# platform_smd2_map2.net
KiCad netlist of a schematic drawn in EAGLE
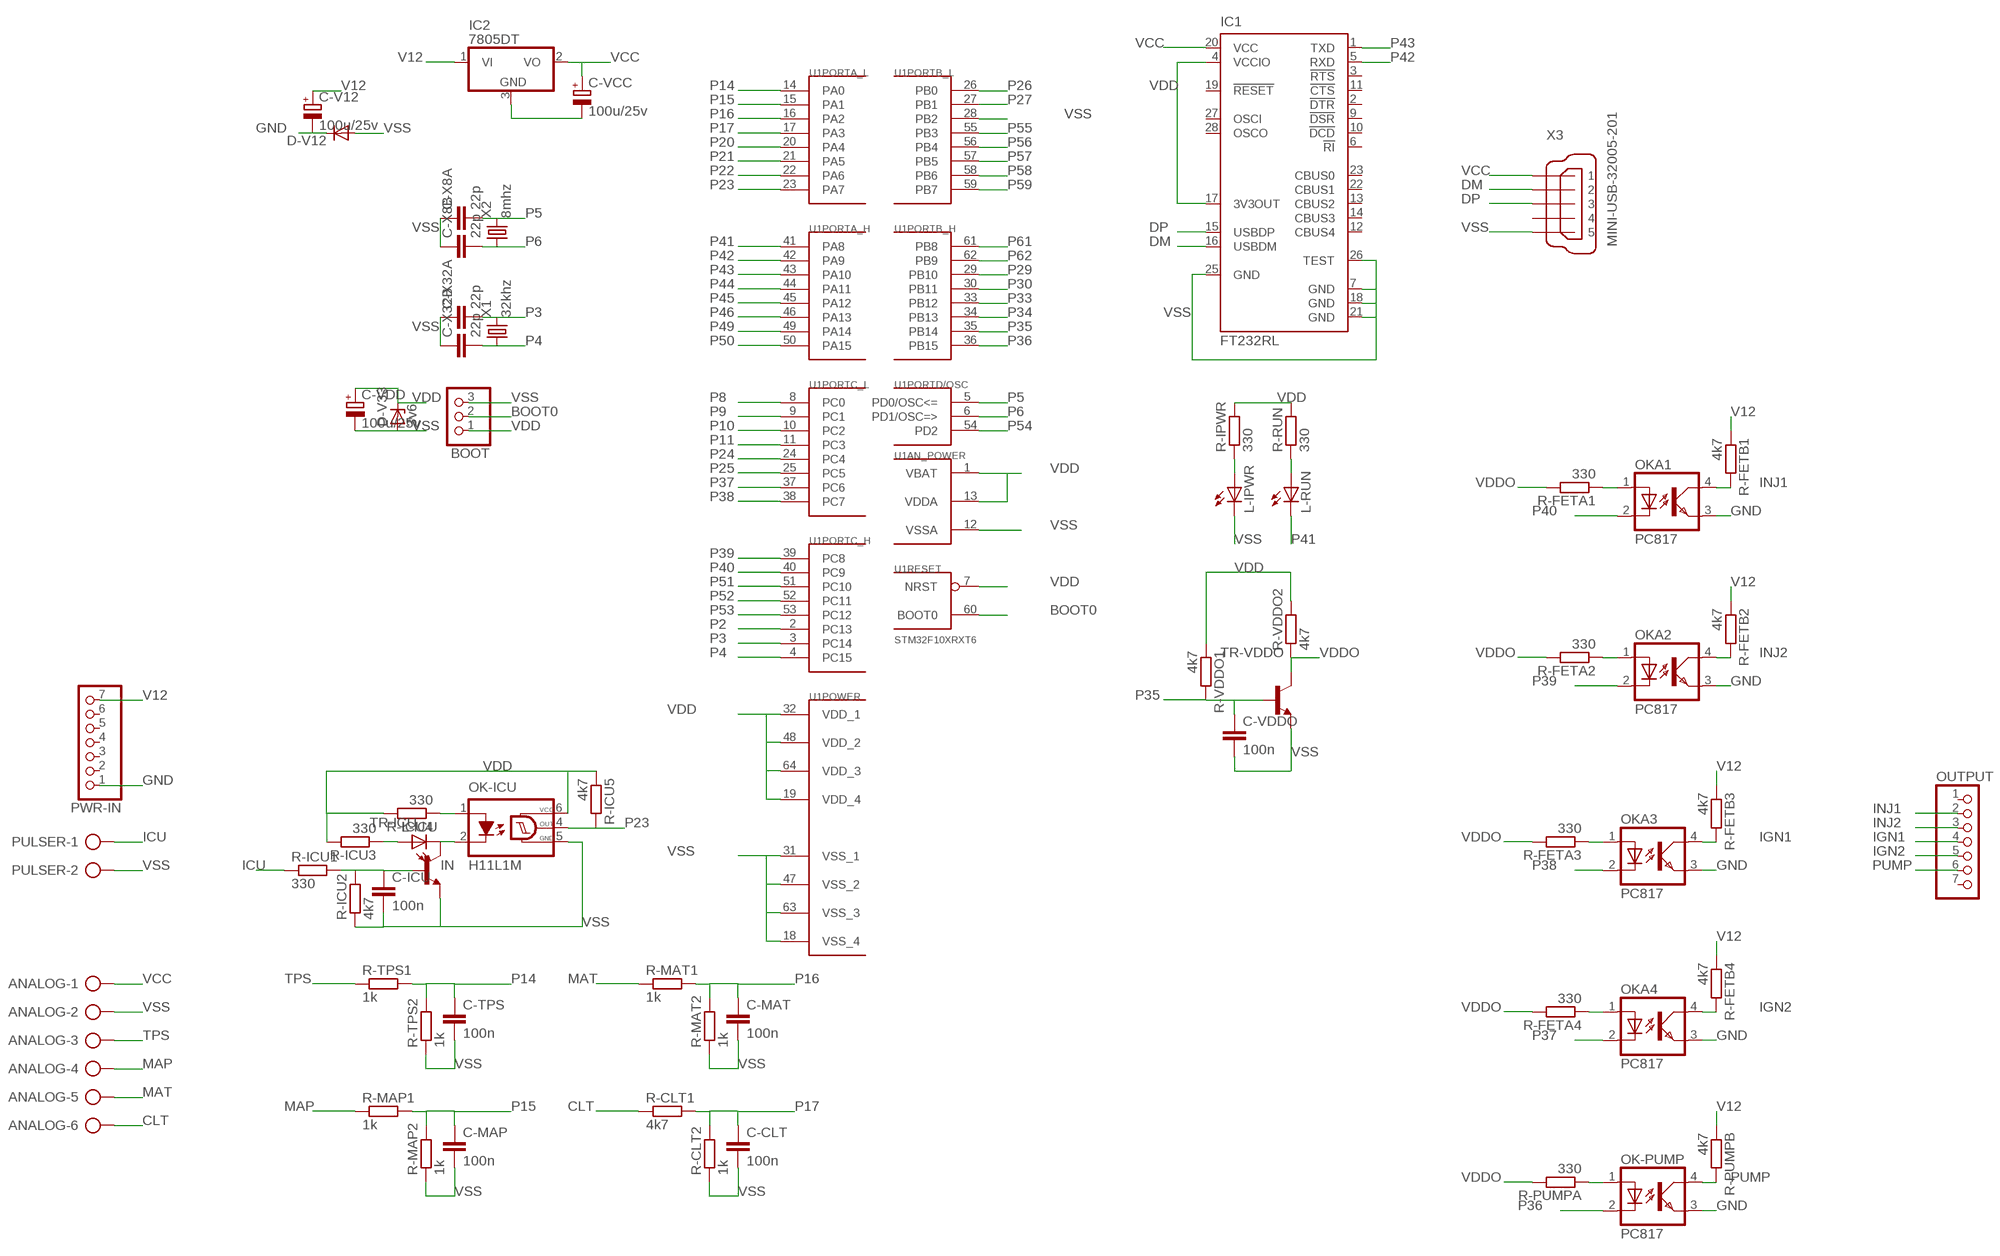
[diagram p0: schematic, sheet 1]

(export (version "E")
  (design (tool "Eeschema 10.0.6"))
  (components
    (comp (ref "ANALOG")
      (value "AK300/6")
      (footprint "eagle-import:AK300_6")
      (libsource (lib "eagle-import") (part "AK300/6"))
    )
    (comp (ref "BOOT")
      (value "PINHD-1X3")
      (footprint "eagle-import:1X03")
      (libsource (lib "eagle-import") (part "PINHD-1X3"))
    )
    (comp (ref "C-CLT")
      (value "100n")
      (footprint "eagle-import:C1206")
      (libsource (lib "eagle-import") (part "C-EUC1206"))
    )
    (comp (ref "C-ICU")
      (value "100n")
      (footprint "eagle-import:C1206")
      (libsource (lib "eagle-import") (part "C-EUC1206"))
    )
    (comp (ref "C-MAP")
      (value "100n")
      (footprint "eagle-import:C1206")
      (libsource (lib "eagle-import") (part "C-EUC1206"))
    )
    (comp (ref "C-MAT")
      (value "100n")
      (footprint "eagle-import:C1206")
      (libsource (lib "eagle-import") (part "C-EUC1206"))
    )
    (comp (ref "C-TPS")
      (value "100n")
      (footprint "eagle-import:C1206")
      (libsource (lib "eagle-import") (part "C-EUC1206"))
    )
    (comp (ref "C-V12")
      (value "100u/25v")
      (footprint "eagle-import:PANASONIC_D")
      (libsource (lib "eagle-import") (part "CPOL-EUD"))
    )
    (comp (ref "C-VCC")
      (value "100u/25v")
      (footprint "eagle-import:PANASONIC_D")
      (libsource (lib "eagle-import") (part "CPOL-EUD"))
    )
    (comp (ref "C-VDD")
      (value "100u/25v")
      (footprint "eagle-import:PANASONIC_D")
      (libsource (lib "eagle-import") (part "CPOL-EUD"))
    )
    (comp (ref "C-VDDO")
      (value "100n")
      (footprint "eagle-import:C1206")
      (libsource (lib "eagle-import") (part "C-EUC1206"))
    )
    (comp (ref "C-X8A")
      (value "22p")
      (footprint "eagle-import:C1206")
      (libsource (lib "eagle-import") (part "C-EUC1206"))
    )
    (comp (ref "C-X8B")
      (value "22p")
      (footprint "eagle-import:C1206")
      (libsource (lib "eagle-import") (part "C-EUC1206"))
    )
    (comp (ref "C-X32A")
      (value "22p")
      (footprint "eagle-import:C1206")
      (libsource (lib "eagle-import") (part "C-EUC1206"))
    )
    (comp (ref "C-X32B")
      (value "22p")
      (footprint "eagle-import:C1206")
      (libsource (lib "eagle-import") (part "C-EUC1206"))
    )
    (comp (ref "D-V12")
      (value "DIODE-SMB")
      (footprint "eagle-import:SMB")
      (libsource (lib "eagle-import") (part "DIODE-SMB"))
    )
    (comp (ref "D-V33")
      (value "3v6")
      (footprint "eagle-import:SMB")
      (libsource (lib "eagle-import") (part "ZENER-DIODESMB"))
    )
    (comp (ref "IC1")
      (value "FT232RL")
      (footprint "eagle-import:SSOP28")
      (libsource (lib "eagle-import") (part "FT232RL"))
    )
    (comp (ref "IC2")
      (value "7805DT")
      (footprint "eagle-import:TO252")
      (libsource (lib "eagle-import") (part "78DT05"))
    )
    (comp (ref "L-ICU")
      (value "LEDSMT1206")
      (footprint "eagle-import:1206")
      (libsource (lib "eagle-import") (part "LEDSMT1206"))
    )
    (comp (ref "L-IPWR")
      (value "LEDSMT1206")
      (footprint "eagle-import:1206")
      (libsource (lib "eagle-import") (part "LEDSMT1206"))
    )
    (comp (ref "L-RUN")
      (value "LEDSMT1206")
      (footprint "eagle-import:1206")
      (libsource (lib "eagle-import") (part "LEDSMT1206"))
    )
    (comp (ref "OK-ICU")
      (value "H11L1M")
      (footprint "eagle-import:DIL06")
      (fields (field (name "MF") "FAIRCHILD SEMICONDUCTOR") (field (name "MPN") "H11L1-M"))
      (libsource (lib "eagle-import") (part "H11LM1"))
    )
    (comp (ref "OK-PUMP")
      (value "PC817")
      (footprint "eagle-import:DIL04")
      (fields (field (name "MPN") "PC817X4J000F"))
      (libsource (lib "eagle-import") (part "PC817"))
    )
    (comp (ref "OKA1")
      (value "PC817")
      (footprint "eagle-import:DIL04")
      (fields (field (name "MPN") "PC817X4J000F"))
      (libsource (lib "eagle-import") (part "PC817"))
    )
    (comp (ref "OKA2")
      (value "PC817")
      (footprint "eagle-import:DIL04")
      (fields (field (name "MPN") "PC817X4J000F"))
      (libsource (lib "eagle-import") (part "PC817"))
    )
    (comp (ref "OKA3")
      (value "PC817")
      (footprint "eagle-import:DIL04")
      (fields (field (name "MPN") "PC817X4J000F"))
      (libsource (lib "eagle-import") (part "PC817"))
    )
    (comp (ref "OKA4")
      (value "PC817")
      (footprint "eagle-import:DIL04")
      (fields (field (name "MPN") "PC817X4J000F"))
      (libsource (lib "eagle-import") (part "PC817"))
    )
    (comp (ref "OUTPUT")
      (value "PINHD-1X7")
      (footprint "eagle-import:1X07")
      (libsource (lib "eagle-import") (part "PINHD-1X7"))
    )
    (comp (ref "PULSER")
      (value "AK300/2")
      (footprint "eagle-import:AK300_2")
      (libsource (lib "eagle-import") (part "AK300/2"))
    )
    (comp (ref "PWR-IN")
      (value "PINHD-1X7")
      (footprint "eagle-import:1X07")
      (libsource (lib "eagle-import") (part "PINHD-1X7"))
    )
    (comp (ref "R-CLT1")
      (value "4k7")
      (footprint "eagle-import:R1206")
      (libsource (lib "eagle-import") (part "R-EU_R1206"))
    )
    (comp (ref "R-CLT2")
      (value "1k")
      (footprint "eagle-import:R1206")
      (libsource (lib "eagle-import") (part "R-EU_R1206"))
    )
    (comp (ref "R-FETA1")
      (value "330")
      (footprint "eagle-import:R1206")
      (libsource (lib "eagle-import") (part "R-EU_R1206"))
    )
    (comp (ref "R-FETA2")
      (value "330")
      (footprint "eagle-import:R1206")
      (libsource (lib "eagle-import") (part "R-EU_R1206"))
    )
    (comp (ref "R-FETA3")
      (value "330")
      (footprint "eagle-import:R1206")
      (libsource (lib "eagle-import") (part "R-EU_R1206"))
    )
    (comp (ref "R-FETA4")
      (value "330")
      (footprint "eagle-import:R1206")
      (libsource (lib "eagle-import") (part "R-EU_R1206"))
    )
    (comp (ref "R-FETB1")
      (value "4k7")
      (footprint "eagle-import:R1206")
      (libsource (lib "eagle-import") (part "R-EU_R1206"))
    )
    (comp (ref "R-FETB2")
      (value "4k7")
      (footprint "eagle-import:R1206")
      (libsource (lib "eagle-import") (part "R-EU_R1206"))
    )
    (comp (ref "R-FETB3")
      (value "4k7")
      (footprint "eagle-import:R1206")
      (libsource (lib "eagle-import") (part "R-EU_R1206"))
    )
    (comp (ref "R-FETB4")
      (value "4k7")
      (footprint "eagle-import:R1206")
      (libsource (lib "eagle-import") (part "R-EU_R1206"))
    )
    (comp (ref "R-ICU1")
      (value "330")
      (footprint "eagle-import:R1206")
      (libsource (lib "eagle-import") (part "R-EU_R1206"))
    )
    (comp (ref "R-ICU2")
      (value "4k7")
      (footprint "eagle-import:R1206")
      (libsource (lib "eagle-import") (part "R-EU_R1206"))
    )
    (comp (ref "R-ICU3")
      (value "330")
      (footprint "eagle-import:R1206")
      (libsource (lib "eagle-import") (part "R-EU_R1206"))
    )
    (comp (ref "R-ICU4")
      (value "330")
      (footprint "eagle-import:R1206")
      (libsource (lib "eagle-import") (part "R-EU_R1206"))
    )
    (comp (ref "R-ICU5")
      (value "4k7")
      (footprint "eagle-import:R1206")
      (libsource (lib "eagle-import") (part "R-EU_R1206"))
    )
    (comp (ref "R-IPWR")
      (value "330")
      (footprint "eagle-import:R1206")
      (libsource (lib "eagle-import") (part "R-EU_R1206"))
    )
    (comp (ref "R-MAP1")
      (value "1k")
      (footprint "eagle-import:R1206")
      (libsource (lib "eagle-import") (part "R-EU_R1206"))
    )
    (comp (ref "R-MAP2")
      (value "1k")
      (footprint "eagle-import:R1206")
      (libsource (lib "eagle-import") (part "R-EU_R1206"))
    )
    (comp (ref "R-MAT1")
      (value "1k")
      (footprint "eagle-import:R1206")
      (libsource (lib "eagle-import") (part "R-EU_R1206"))
    )
    (comp (ref "R-MAT2")
      (value "1k")
      (footprint "eagle-import:R1206")
      (libsource (lib "eagle-import") (part "R-EU_R1206"))
    )
    (comp (ref "R-PUMPA")
      (value "330")
      (footprint "eagle-import:R1206")
      (libsource (lib "eagle-import") (part "R-EU_R1206"))
    )
    (comp (ref "R-PUMPB")
      (value "4k7")
      (footprint "eagle-import:R1206")
      (libsource (lib "eagle-import") (part "R-EU_R1206"))
    )
    (comp (ref "R-RUN")
      (value "330")
      (footprint "eagle-import:R1206")
      (libsource (lib "eagle-import") (part "R-EU_R1206"))
    )
    (comp (ref "R-TPS1")
      (value "1k")
      (footprint "eagle-import:R1206")
      (libsource (lib "eagle-import") (part "R-EU_R1206"))
    )
    (comp (ref "R-TPS2")
      (value "1k")
      (footprint "eagle-import:R1206")
      (libsource (lib "eagle-import") (part "R-EU_R1206"))
    )
    (comp (ref "R-VDDO1")
      (value "4k7")
      (footprint "eagle-import:M1206")
      (libsource (lib "eagle-import") (part "R-EU_M1206"))
    )
    (comp (ref "R-VDDO2")
      (value "4k7")
      (footprint "eagle-import:M1206")
      (libsource (lib "eagle-import") (part "R-EU_M1206"))
    )
    (comp (ref "TR-ICU")
      (value "MMBT3904LT1-NPN-SOT23-BEC")
      (footprint "eagle-import:SOT23-BEC")
      (libsource (lib "eagle-import") (part "-NPN-SOT23-BECMMBT3904LT1"))
    )
    (comp (ref "TR-VDDO")
      (value "MMBT3904LT1-NPN-SOT23-BEC")
      (footprint "eagle-import:SOT23-BEC")
      (libsource (lib "eagle-import") (part "-NPN-SOT23-BECMMBT3904LT1"))
    )
    (comp (ref "U1")
      (value "STM32F10XRXT6")
      (footprint "eagle-import:TQFP64")
      (libsource (lib "eagle-import") (part "STM32F10XRXT6"))
    )
    (comp (ref "X1")
      (value "32khz")
      (footprint "eagle-import:TC26V")
      (libsource (lib "eagle-import") (part "CRYSTALTC26V"))
    )
    (comp (ref "X2")
      (value "8mhz")
      (footprint "eagle-import:HC49U-V")
      (libsource (lib "eagle-import") (part "CRYSTALHC49U-V"))
    )
    (comp (ref "X3")
      (value "MINI-USB-32005-201")
      (footprint "eagle-import:32005-201")
      (libsource (lib "eagle-import") (part "MINI-USB-32005-201"))
    )
  )
  (nets
    (net (code "1") (name "/BOOT0") (class "Default")
      (node (ref "BOOT") (pin "2") (pinfunction "2_2") (pintype "passive"))
      (node (ref "U1") (pin "60") (pinfunction "BOOT0_60") (pintype "input"))
    )
    (net (code "2") (name "/CLT") (class "Default")
      (node (ref "ANALOG") (pin "6") (pinfunction "KL_6") (pintype "passive"))
      (node (ref "R-CLT1") (pin "1") (pinfunction "1_1") (pintype "passive"))
    )
    (net (code "3") (name "/DM") (class "Default")
      (node (ref "IC1") (pin "16") (pinfunction "USBDM_16") (pintype "bidirectional"))
      (node (ref "X3") (pin "2") (pinfunction "2_2") (pintype "passive"))
    )
    (net (code "4") (name "/DP") (class "Default")
      (node (ref "IC1") (pin "15") (pinfunction "USBDP_15") (pintype "bidirectional"))
      (node (ref "X3") (pin "3") (pinfunction "3_3") (pintype "passive"))
    )
    (net (code "5") (name "/GND") (class "Default")
      (node (ref "C-V12") (pin "-") (pinfunction "-_-") (pintype "passive"))
      (node (ref "D-V12") (pin "C") (pinfunction "C_C") (pintype "passive"))
      (node (ref "OK-PUMP") (pin "3") (pinfunction "EMIT_3") (pintype "passive"))
      (node (ref "OKA1") (pin "3") (pinfunction "EMIT_3") (pintype "passive"))
      (node (ref "OKA2") (pin "3") (pinfunction "EMIT_3") (pintype "passive"))
      (node (ref "OKA3") (pin "3") (pinfunction "EMIT_3") (pintype "passive"))
      (node (ref "OKA4") (pin "3") (pinfunction "EMIT_3") (pintype "passive"))
      (node (ref "PWR-IN") (pin "1") (pinfunction "1_1") (pintype "passive"))
    )
    (net (code "6") (name "/ICU") (class "Default")
      (node (ref "PULSER") (pin "1") (pinfunction "KL_1") (pintype "passive"))
      (node (ref "R-ICU1") (pin "1") (pinfunction "1_1") (pintype "passive"))
    )
    (net (code "7") (name "/IGN1") (class "Default")
      (node (ref "OKA3") (pin "4") (pinfunction "COL_4") (pintype "passive"))
      (node (ref "OUTPUT") (pin "4") (pinfunction "4_4") (pintype "passive"))
      (node (ref "R-FETB3") (pin "2") (pinfunction "2_2") (pintype "passive"))
    )
    (net (code "8") (name "/IGN2") (class "Default")
      (node (ref "OKA4") (pin "4") (pinfunction "COL_4") (pintype "passive"))
      (node (ref "OUTPUT") (pin "5") (pinfunction "5_5") (pintype "passive"))
      (node (ref "R-FETB4") (pin "2") (pinfunction "2_2") (pintype "passive"))
    )
    (net (code "9") (name "/IN") (class "Default")
      (node (ref "L-ICU") (pin "C") (pinfunction "C_C") (pintype "passive"))
      (node (ref "OK-ICU") (pin "2") (pinfunction "C_2") (pintype "passive"))
      (node (ref "TR-ICU") (pin "C") (pinfunction "C_C") (pintype "passive"))
    )
    (net (code "10") (name "/INJ1") (class "Default")
      (node (ref "OKA1") (pin "4") (pinfunction "COL_4") (pintype "passive"))
      (node (ref "OUTPUT") (pin "2") (pinfunction "2_2") (pintype "passive"))
      (node (ref "R-FETB1") (pin "2") (pinfunction "2_2") (pintype "passive"))
    )
    (net (code "11") (name "/INJ2") (class "Default")
      (node (ref "OKA2") (pin "4") (pinfunction "COL_4") (pintype "passive"))
      (node (ref "OUTPUT") (pin "3") (pinfunction "3_3") (pintype "passive"))
      (node (ref "R-FETB2") (pin "2") (pinfunction "2_2") (pintype "passive"))
    )
    (net (code "12") (name "/MAP") (class "Default")
      (node (ref "ANALOG") (pin "4") (pinfunction "KL_4") (pintype "passive"))
      (node (ref "R-MAP1") (pin "1") (pinfunction "1_1") (pintype "passive"))
    )
    (net (code "13") (name "/MAT") (class "Default")
      (node (ref "ANALOG") (pin "5") (pinfunction "KL_5") (pintype "passive"))
      (node (ref "R-MAT1") (pin "1") (pinfunction "1_1") (pintype "passive"))
    )
    (net (code "14") (name "/P2") (class "Default")
      (node (ref "U1") (pin "2") (pinfunction "PC13_2") (pintype "bidirectional"))
    )
    (net (code "15") (name "/P3") (class "Default")
      (node (ref "C-X32A") (pin "2") (pinfunction "2_2") (pintype "passive"))
      (node (ref "U1") (pin "3") (pinfunction "PC14_3") (pintype "bidirectional"))
      (node (ref "X1") (pin "2") (pinfunction "2_2") (pintype "passive"))
    )
    (net (code "16") (name "/P4") (class "Default")
      (node (ref "C-X32B") (pin "2") (pinfunction "2_2") (pintype "passive"))
      (node (ref "U1") (pin "4") (pinfunction "PC15_4") (pintype "bidirectional"))
      (node (ref "X1") (pin "1") (pinfunction "1_1") (pintype "passive"))
    )
    (net (code "17") (name "/P5") (class "Default")
      (node (ref "C-X8A") (pin "2") (pinfunction "2_2") (pintype "passive"))
      (node (ref "U1") (pin "5") (pinfunction "PD0/OSC<=_5") (pintype "bidirectional"))
      (node (ref "X2") (pin "2") (pinfunction "2_2") (pintype "passive"))
    )
    (net (code "18") (name "/P6") (class "Default")
      (node (ref "C-X8B") (pin "2") (pinfunction "2_2") (pintype "passive"))
      (node (ref "U1") (pin "6") (pinfunction "PD1/OSC=>_6") (pintype "bidirectional"))
      (node (ref "X2") (pin "1") (pinfunction "1_1") (pintype "passive"))
    )
    (net (code "19") (name "/P8") (class "Default")
      (node (ref "U1") (pin "8") (pinfunction "PC0_8") (pintype "bidirectional"))
    )
    (net (code "20") (name "/P9") (class "Default")
      (node (ref "U1") (pin "9") (pinfunction "PC1_9") (pintype "bidirectional"))
    )
    (net (code "21") (name "/P10") (class "Default")
      (node (ref "U1") (pin "10") (pinfunction "PC2_10") (pintype "bidirectional"))
    )
    (net (code "22") (name "/P11") (class "Default")
      (node (ref "U1") (pin "11") (pinfunction "PC3_11") (pintype "bidirectional"))
    )
    (net (code "23") (name "/P14") (class "Default")
      (node (ref "C-TPS") (pin "1") (pinfunction "1_1") (pintype "passive"))
      (node (ref "R-TPS1") (pin "2") (pinfunction "2_2") (pintype "passive"))
      (node (ref "R-TPS2") (pin "2") (pinfunction "2_2") (pintype "passive"))
      (node (ref "U1") (pin "14") (pinfunction "PA0_14") (pintype "bidirectional"))
    )
    (net (code "24") (name "/P15") (class "Default")
      (node (ref "C-MAP") (pin "1") (pinfunction "1_1") (pintype "passive"))
      (node (ref "R-MAP1") (pin "2") (pinfunction "2_2") (pintype "passive"))
      (node (ref "R-MAP2") (pin "2") (pinfunction "2_2") (pintype "passive"))
      (node (ref "U1") (pin "15") (pinfunction "PA1_15") (pintype "bidirectional"))
    )
    (net (code "25") (name "/P16") (class "Default")
      (node (ref "C-MAT") (pin "1") (pinfunction "1_1") (pintype "passive"))
      (node (ref "R-MAT1") (pin "2") (pinfunction "2_2") (pintype "passive"))
      (node (ref "R-MAT2") (pin "2") (pinfunction "2_2") (pintype "passive"))
      (node (ref "U1") (pin "16") (pinfunction "PA2_16") (pintype "bidirectional"))
    )
    (net (code "26") (name "/P17") (class "Default")
      (node (ref "C-CLT") (pin "1") (pinfunction "1_1") (pintype "passive"))
      (node (ref "R-CLT1") (pin "2") (pinfunction "2_2") (pintype "passive"))
      (node (ref "R-CLT2") (pin "2") (pinfunction "2_2") (pintype "passive"))
      (node (ref "U1") (pin "17") (pinfunction "PA3_17") (pintype "bidirectional"))
    )
    (net (code "27") (name "/P20") (class "Default")
      (node (ref "U1") (pin "20") (pinfunction "PA4_20") (pintype "bidirectional"))
    )
    (net (code "28") (name "/P21") (class "Default")
      (node (ref "U1") (pin "21") (pinfunction "PA5_21") (pintype "bidirectional"))
    )
    (net (code "29") (name "/P22") (class "Default")
      (node (ref "U1") (pin "22") (pinfunction "PA6_22") (pintype "bidirectional"))
    )
    (net (code "30") (name "/P23") (class "Default")
      (node (ref "OK-ICU") (pin "4") (pinfunction "OUT_4") (pintype "output"))
      (node (ref "R-ICU5") (pin "2") (pinfunction "2_2") (pintype "passive"))
      (node (ref "U1") (pin "23") (pinfunction "PA7_23") (pintype "bidirectional"))
    )
    (net (code "31") (name "/P24") (class "Default")
      (node (ref "U1") (pin "24") (pinfunction "PC4_24") (pintype "bidirectional"))
    )
    (net (code "32") (name "/P25") (class "Default")
      (node (ref "U1") (pin "25") (pinfunction "PC5_25") (pintype "bidirectional"))
    )
    (net (code "33") (name "/P26") (class "Default")
      (node (ref "U1") (pin "26") (pinfunction "PB0_26") (pintype "bidirectional"))
    )
    (net (code "34") (name "/P27") (class "Default")
      (node (ref "U1") (pin "27") (pinfunction "PB1_27") (pintype "bidirectional"))
    )
    (net (code "35") (name "/P29") (class "Default")
      (node (ref "U1") (pin "29") (pinfunction "PB10_29") (pintype "bidirectional"))
    )
    (net (code "36") (name "/P30") (class "Default")
      (node (ref "U1") (pin "30") (pinfunction "PB11_30") (pintype "bidirectional"))
    )
    (net (code "37") (name "/P33") (class "Default")
      (node (ref "U1") (pin "33") (pinfunction "PB12_33") (pintype "bidirectional"))
    )
    (net (code "38") (name "/P34") (class "Default")
      (node (ref "U1") (pin "34") (pinfunction "PB13_34") (pintype "bidirectional"))
    )
    (net (code "39") (name "/P35") (class "Default")
      (node (ref "C-VDDO") (pin "1") (pinfunction "1_1") (pintype "passive"))
      (node (ref "R-VDDO1") (pin "2") (pinfunction "2_2") (pintype "passive"))
      (node (ref "TR-VDDO") (pin "B") (pinfunction "B_B") (pintype "passive"))
      (node (ref "U1") (pin "35") (pinfunction "PB14_35") (pintype "bidirectional"))
    )
    (net (code "40") (name "/P36") (class "Default")
      (node (ref "OK-PUMP") (pin "2") (pinfunction "C_2") (pintype "passive"))
      (node (ref "U1") (pin "36") (pinfunction "PB15_36") (pintype "bidirectional"))
    )
    (net (code "41") (name "/P37") (class "Default")
      (node (ref "OKA4") (pin "2") (pinfunction "C_2") (pintype "passive"))
      (node (ref "U1") (pin "37") (pinfunction "PC6_37") (pintype "bidirectional"))
    )
    (net (code "42") (name "/P38") (class "Default")
      (node (ref "OKA3") (pin "2") (pinfunction "C_2") (pintype "passive"))
      (node (ref "U1") (pin "38") (pinfunction "PC7_38") (pintype "bidirectional"))
    )
    (net (code "43") (name "/P39") (class "Default")
      (node (ref "OKA2") (pin "2") (pinfunction "C_2") (pintype "passive"))
      (node (ref "U1") (pin "39") (pinfunction "PC8_39") (pintype "bidirectional"))
    )
    (net (code "44") (name "/P40") (class "Default")
      (node (ref "OKA1") (pin "2") (pinfunction "C_2") (pintype "passive"))
      (node (ref "U1") (pin "40") (pinfunction "PC9_40") (pintype "bidirectional"))
    )
    (net (code "45") (name "/P41") (class "Default")
      (node (ref "L-RUN") (pin "C") (pinfunction "C_C") (pintype "passive"))
      (node (ref "U1") (pin "41") (pinfunction "PA8_41") (pintype "bidirectional"))
    )
    (net (code "46") (name "/P42") (class "Default")
      (node (ref "IC1") (pin "5") (pinfunction "RXD_5") (pintype "input"))
      (node (ref "U1") (pin "42") (pinfunction "PA9_42") (pintype "bidirectional"))
    )
    (net (code "47") (name "/P43") (class "Default")
      (node (ref "IC1") (pin "1") (pinfunction "TXD_1") (pintype "output"))
      (node (ref "U1") (pin "43") (pinfunction "PA10_43") (pintype "bidirectional"))
    )
    (net (code "48") (name "/P44") (class "Default")
      (node (ref "U1") (pin "44") (pinfunction "PA11_44") (pintype "bidirectional"))
    )
    (net (code "49") (name "/P45") (class "Default")
      (node (ref "U1") (pin "45") (pinfunction "PA12_45") (pintype "bidirectional"))
    )
    (net (code "50") (name "/P46") (class "Default")
      (node (ref "U1") (pin "46") (pinfunction "PA13_46") (pintype "bidirectional"))
    )
    (net (code "51") (name "/P49") (class "Default")
      (node (ref "U1") (pin "49") (pinfunction "PA14_49") (pintype "bidirectional"))
    )
    (net (code "52") (name "/P50") (class "Default")
      (node (ref "U1") (pin "50") (pinfunction "PA15_50") (pintype "bidirectional"))
    )
    (net (code "53") (name "/P51") (class "Default")
      (node (ref "U1") (pin "51") (pinfunction "PC10_51") (pintype "bidirectional"))
    )
    (net (code "54") (name "/P52") (class "Default")
      (node (ref "U1") (pin "52") (pinfunction "PC11_52") (pintype "bidirectional"))
    )
    (net (code "55") (name "/P53") (class "Default")
      (node (ref "U1") (pin "53") (pinfunction "PC12_53") (pintype "bidirectional"))
    )
    (net (code "56") (name "/P54") (class "Default")
      (node (ref "U1") (pin "54") (pinfunction "PD2_54") (pintype "bidirectional"))
    )
    (net (code "57") (name "/P55") (class "Default")
      (node (ref "U1") (pin "55") (pinfunction "PB3_55") (pintype "bidirectional"))
    )
    (net (code "58") (name "/P56") (class "Default")
      (node (ref "U1") (pin "56") (pinfunction "PB4_56") (pintype "bidirectional"))
    )
    (net (code "59") (name "/P57") (class "Default")
      (node (ref "U1") (pin "57") (pinfunction "PB5_57") (pintype "bidirectional"))
    )
    (net (code "60") (name "/P58") (class "Default")
      (node (ref "U1") (pin "58") (pinfunction "PB6_58") (pintype "bidirectional"))
    )
    (net (code "61") (name "/P59") (class "Default")
      (node (ref "U1") (pin "59") (pinfunction "PB7_59") (pintype "bidirectional"))
    )
    (net (code "62") (name "/P61") (class "Default")
      (node (ref "U1") (pin "61") (pinfunction "PB8_61") (pintype "bidirectional"))
    )
    (net (code "63") (name "/P62") (class "Default")
      (node (ref "U1") (pin "62") (pinfunction "PB9_62") (pintype "bidirectional"))
    )
    (net (code "64") (name "/PUMP") (class "Default")
      (node (ref "OK-PUMP") (pin "4") (pinfunction "COL_4") (pintype "passive"))
      (node (ref "OUTPUT") (pin "6") (pinfunction "6_6") (pintype "passive"))
      (node (ref "R-PUMPB") (pin "2") (pinfunction "2_2") (pintype "passive"))
    )
    (net (code "65") (name "/TPS") (class "Default")
      (node (ref "ANALOG") (pin "3") (pinfunction "KL_3") (pintype "passive"))
      (node (ref "R-TPS1") (pin "1") (pinfunction "1_1") (pintype "passive"))
    )
    (net (code "66") (name "/V12") (class "Default")
      (node (ref "C-V12") (pin "+") (pinfunction "+_+") (pintype "passive"))
      (node (ref "IC2") (pin "1") (pinfunction "VI_1") (pintype "input"))
      (node (ref "PWR-IN") (pin "7") (pinfunction "7_7") (pintype "passive"))
      (node (ref "R-FETB1") (pin "1") (pinfunction "1_1") (pintype "passive"))
      (node (ref "R-FETB2") (pin "1") (pinfunction "1_1") (pintype "passive"))
      (node (ref "R-FETB3") (pin "1") (pinfunction "1_1") (pintype "passive"))
      (node (ref "R-FETB4") (pin "1") (pinfunction "1_1") (pintype "passive"))
      (node (ref "R-PUMPB") (pin "1") (pinfunction "1_1") (pintype "passive"))
    )
    (net (code "67") (name "/VCC") (class "Default")
      (node (ref "ANALOG") (pin "1") (pinfunction "KL_1") (pintype "passive"))
      (node (ref "C-VCC") (pin "+") (pinfunction "+_+") (pintype "passive"))
      (node (ref "IC1") (pin "20") (pinfunction "VCC_20") (pintype "power_in"))
      (node (ref "IC2") (pin "2") (pinfunction "VO_2") (pintype "passive"))
      (node (ref "X3") (pin "1") (pinfunction "1_1") (pintype "passive"))
    )
    (net (code "68") (name "/VDD") (class "Default")
      (node (ref "BOOT") (pin "1") (pinfunction "1_1") (pintype "passive"))
      (node (ref "C-VDD") (pin "+") (pinfunction "+_+") (pintype "passive"))
      (node (ref "D-V33") (pin "C") (pinfunction "C_C") (pintype "passive"))
      (node (ref "IC1") (pin "17") (pinfunction "3V3OUT_17") (pintype "output"))
      (node (ref "IC1") (pin "4") (pinfunction "VCCIO_4") (pintype "power_in"))
      (node (ref "OK-ICU") (pin "6") (pinfunction "VCC_6") (pintype "power_in"))
      (node (ref "R-ICU3") (pin "2") (pinfunction "2_2") (pintype "passive"))
      (node (ref "R-ICU4") (pin "2") (pinfunction "2_2") (pintype "passive"))
      (node (ref "R-ICU5") (pin "1") (pinfunction "1_1") (pintype "passive"))
      (node (ref "R-IPWR") (pin "2") (pinfunction "2_2") (pintype "passive"))
      (node (ref "R-RUN") (pin "2") (pinfunction "2_2") (pintype "passive"))
      (node (ref "R-VDDO1") (pin "1") (pinfunction "1_1") (pintype "passive"))
      (node (ref "R-VDDO2") (pin "2") (pinfunction "2_2") (pintype "passive"))
      (node (ref "U1") (pin "1") (pinfunction "VBAT_1") (pintype "power_in"))
      (node (ref "U1") (pin "13") (pinfunction "VDDA_13") (pintype "power_in"))
      (node (ref "U1") (pin "19") (pinfunction "VDD_4_19") (pintype "power_in"))
      (node (ref "U1") (pin "32") (pinfunction "VDD_1_32") (pintype "power_in"))
      (node (ref "U1") (pin "48") (pinfunction "VDD_2_48") (pintype "power_in"))
      (node (ref "U1") (pin "64") (pinfunction "VDD_3_64") (pintype "power_in"))
      (node (ref "U1") (pin "7") (pinfunction "NRST_7") (pintype "input"))
    )
    (net (code "69") (name "/VDDO") (class "Default")
      (node (ref "R-FETA1") (pin "2") (pinfunction "2_2") (pintype "passive"))
      (node (ref "R-FETA2") (pin "2") (pinfunction "2_2") (pintype "passive"))
      (node (ref "R-FETA3") (pin "2") (pinfunction "2_2") (pintype "passive"))
      (node (ref "R-FETA4") (pin "2") (pinfunction "2_2") (pintype "passive"))
      (node (ref "R-PUMPA") (pin "2") (pinfunction "2_2") (pintype "passive"))
      (node (ref "R-VDDO2") (pin "1") (pinfunction "1_1") (pintype "passive"))
      (node (ref "TR-VDDO") (pin "C") (pinfunction "C_C") (pintype "passive"))
    )
    (net (code "70") (name "/VSS") (class "Default")
      (node (ref "ANALOG") (pin "2") (pinfunction "KL_2") (pintype "passive"))
      (node (ref "BOOT") (pin "3") (pinfunction "3_3") (pintype "passive"))
      (node (ref "C-CLT") (pin "2") (pinfunction "2_2") (pintype "passive"))
      (node (ref "C-ICU") (pin "2") (pinfunction "2_2") (pintype "passive"))
      (node (ref "C-MAP") (pin "2") (pinfunction "2_2") (pintype "passive"))
      (node (ref "C-MAT") (pin "2") (pinfunction "2_2") (pintype "passive"))
      (node (ref "C-TPS") (pin "2") (pinfunction "2_2") (pintype "passive"))
      (node (ref "C-VCC") (pin "-") (pinfunction "-_-") (pintype "passive"))
      (node (ref "C-VDD") (pin "-") (pinfunction "-_-") (pintype "passive"))
      (node (ref "C-VDDO") (pin "2") (pinfunction "2_2") (pintype "passive"))
      (node (ref "C-X32A") (pin "1") (pinfunction "1_1") (pintype "passive"))
      (node (ref "C-X32B") (pin "1") (pinfunction "1_1") (pintype "passive"))
      (node (ref "C-X8A") (pin "1") (pinfunction "1_1") (pintype "passive"))
      (node (ref "C-X8B") (pin "1") (pinfunction "1_1") (pintype "passive"))
      (node (ref "D-V12") (pin "A") (pinfunction "A_A") (pintype "passive"))
      (node (ref "D-V33") (pin "A") (pinfunction "A_A") (pintype "passive"))
      (node (ref "IC1") (pin "18") (pinfunction "GND_18") (pintype "power_in"))
      (node (ref "IC1") (pin "21") (pinfunction "GND_21") (pintype "power_in"))
      (node (ref "IC1") (pin "25") (pinfunction "GND_25") (pintype "power_in"))
      (node (ref "IC1") (pin "26") (pinfunction "TEST_26") (pintype "input"))
      (node (ref "IC1") (pin "7") (pinfunction "GND_7") (pintype "power_in"))
      (node (ref "IC2") (pin "3") (pinfunction "GND_3") (pintype "passive"))
      (node (ref "L-IPWR") (pin "C") (pinfunction "C_C") (pintype "passive"))
      (node (ref "OK-ICU") (pin "5") (pinfunction "GND_5") (pintype "power_in"))
      (node (ref "PULSER") (pin "2") (pinfunction "KL_2") (pintype "passive"))
      (node (ref "R-CLT2") (pin "1") (pinfunction "1_1") (pintype "passive"))
      (node (ref "R-ICU2") (pin "1") (pinfunction "1_1") (pintype "passive"))
      (node (ref "R-MAP2") (pin "1") (pinfunction "1_1") (pintype "passive"))
      (node (ref "R-MAT2") (pin "1") (pinfunction "1_1") (pintype "passive"))
      (node (ref "R-TPS2") (pin "1") (pinfunction "1_1") (pintype "passive"))
      (node (ref "TR-ICU") (pin "E") (pinfunction "E_E") (pintype "passive"))
      (node (ref "TR-VDDO") (pin "E") (pinfunction "E_E") (pintype "passive"))
      (node (ref "U1") (pin "12") (pinfunction "VSSA_12") (pintype "power_in"))
      (node (ref "U1") (pin "18") (pinfunction "VSS_4_18") (pintype "power_in"))
      (node (ref "U1") (pin "28") (pinfunction "PB2_28") (pintype "bidirectional"))
      (node (ref "U1") (pin "31") (pinfunction "VSS_1_31") (pintype "power_in"))
      (node (ref "U1") (pin "47") (pinfunction "VSS_2_47") (pintype "power_in"))
      (node (ref "U1") (pin "63") (pinfunction "VSS_3_63") (pintype "power_in"))
      (node (ref "X3") (pin "5") (pinfunction "5_5") (pintype "passive"))
    )
    (net (code "71") (name "Net-(C-ICU-Pad1)") (class "Default")
      (node (ref "C-ICU") (pin "1") (pinfunction "1_1") (pintype "passive"))
      (node (ref "R-ICU1") (pin "2") (pinfunction "2_2") (pintype "passive"))
      (node (ref "R-ICU2") (pin "2") (pinfunction "2_2") (pintype "passive"))
      (node (ref "TR-ICU") (pin "B") (pinfunction "B_B") (pintype "passive"))
    )
    (net (code "72") (name "Net-(L-ICU-PadA)") (class "Default")
      (node (ref "L-ICU") (pin "A") (pinfunction "A_A") (pintype "passive"))
      (node (ref "R-ICU3") (pin "1") (pinfunction "1_1") (pintype "passive"))
    )
    (net (code "73") (name "Net-(L-IPWR-PadA)") (class "Default")
      (node (ref "L-IPWR") (pin "A") (pinfunction "A_A") (pintype "passive"))
      (node (ref "R-IPWR") (pin "1") (pinfunction "1_1") (pintype "passive"))
    )
    (net (code "74") (name "Net-(L-RUN-PadA)") (class "Default")
      (node (ref "L-RUN") (pin "A") (pinfunction "A_A") (pintype "passive"))
      (node (ref "R-RUN") (pin "1") (pinfunction "1_1") (pintype "passive"))
    )
    (net (code "75") (name "Net-(OK-ICU-A)") (class "Default")
      (node (ref "OK-ICU") (pin "1") (pinfunction "A_1") (pintype "passive"))
      (node (ref "R-ICU4") (pin "1") (pinfunction "1_1") (pintype "passive"))
    )
    (net (code "76") (name "Net-(OK-PUMP-A)") (class "Default")
      (node (ref "OK-PUMP") (pin "1") (pinfunction "A_1") (pintype "passive"))
      (node (ref "R-PUMPA") (pin "1") (pinfunction "1_1") (pintype "passive"))
    )
    (net (code "77") (name "Net-(OKA1-A)") (class "Default")
      (node (ref "OKA1") (pin "1") (pinfunction "A_1") (pintype "passive"))
      (node (ref "R-FETA1") (pin "1") (pinfunction "1_1") (pintype "passive"))
    )
    (net (code "78") (name "Net-(OKA2-A)") (class "Default")
      (node (ref "OKA2") (pin "1") (pinfunction "A_1") (pintype "passive"))
      (node (ref "R-FETA2") (pin "1") (pinfunction "1_1") (pintype "passive"))
    )
    (net (code "79") (name "Net-(OKA3-A)") (class "Default")
      (node (ref "OKA3") (pin "1") (pinfunction "A_1") (pintype "passive"))
      (node (ref "R-FETA3") (pin "1") (pinfunction "1_1") (pintype "passive"))
    )
    (net (code "80") (name "Net-(OKA4-A)") (class "Default")
      (node (ref "OKA4") (pin "1") (pinfunction "A_1") (pintype "passive"))
      (node (ref "R-FETA4") (pin "1") (pinfunction "1_1") (pintype "passive"))
    )
    (net (code "81") (name "unconnected-(IC1-CBUS0-Pad23)") (class "Default")
      (node (ref "IC1") (pin "23") (pinfunction "CBUS0_23") (pintype "bidirectional"))
    )
    (net (code "82") (name "unconnected-(IC1-CBUS1-Pad22)") (class "Default")
      (node (ref "IC1") (pin "22") (pinfunction "CBUS1_22") (pintype "bidirectional"))
    )
    (net (code "83") (name "unconnected-(IC1-CBUS2-Pad13)") (class "Default")
      (node (ref "IC1") (pin "13") (pinfunction "CBUS2_13") (pintype "bidirectional"))
    )
    (net (code "84") (name "unconnected-(IC1-CBUS3-Pad14)") (class "Default")
      (node (ref "IC1") (pin "14") (pinfunction "CBUS3_14") (pintype "bidirectional"))
    )
    (net (code "85") (name "unconnected-(IC1-CBUS4-Pad12)") (class "Default")
      (node (ref "IC1") (pin "12") (pinfunction "CBUS4_12") (pintype "bidirectional"))
    )
    (net (code "86") (name "unconnected-(IC1-OSCI-Pad27)") (class "Default")
      (node (ref "IC1") (pin "27") (pinfunction "OSCI_27") (pintype "input"))
    )
    (net (code "87") (name "unconnected-(IC1-OSCO-Pad28)") (class "Default")
      (node (ref "IC1") (pin "28") (pinfunction "OSCO_28") (pintype "output"))
    )
    (net (code "88") (name "unconnected-(IC1-~{CTS}-Pad11)") (class "Default")
      (node (ref "IC1") (pin "11") (pinfunction "~{CTS}_11") (pintype "input"))
    )
    (net (code "89") (name "unconnected-(IC1-~{DCD}-Pad10)") (class "Default")
      (node (ref "IC1") (pin "10") (pinfunction "~{DCD}_10") (pintype "input"))
    )
    (net (code "90") (name "unconnected-(IC1-~{DSR}-Pad9)") (class "Default")
      (node (ref "IC1") (pin "9") (pinfunction "~{DSR}_9") (pintype "input"))
    )
    (net (code "91") (name "unconnected-(IC1-~{DTR}-Pad2)") (class "Default")
      (node (ref "IC1") (pin "2") (pinfunction "~{DTR}_2") (pintype "output"))
    )
    (net (code "92") (name "unconnected-(IC1-~{RESET}-Pad19)") (class "Default")
      (node (ref "IC1") (pin "19") (pinfunction "~{RESET}_19") (pintype "input"))
    )
    (net (code "93") (name "unconnected-(IC1-~{RI}-Pad6)") (class "Default")
      (node (ref "IC1") (pin "6") (pinfunction "~{RI}_6") (pintype "input"))
    )
    (net (code "94") (name "unconnected-(IC1-~{RTS}-Pad3)") (class "Default")
      (node (ref "IC1") (pin "3") (pinfunction "~{RTS}_3") (pintype "output"))
    )
    (net (code "95") (name "unconnected-(OUTPUT-Pad1)") (class "Default")
      (node (ref "OUTPUT") (pin "1") (pinfunction "1_1") (pintype "passive"))
    )
    (net (code "96") (name "unconnected-(OUTPUT-Pad7)") (class "Default")
      (node (ref "OUTPUT") (pin "7") (pinfunction "7_7") (pintype "passive"))
    )
    (net (code "97") (name "unconnected-(PWR-IN-Pad2)") (class "Default")
      (node (ref "PWR-IN") (pin "2") (pinfunction "2_2") (pintype "passive"))
    )
    (net (code "98") (name "unconnected-(PWR-IN-Pad3)") (class "Default")
      (node (ref "PWR-IN") (pin "3") (pinfunction "3_3") (pintype "passive"))
    )
    (net (code "99") (name "unconnected-(PWR-IN-Pad4)") (class "Default")
      (node (ref "PWR-IN") (pin "4") (pinfunction "4_4") (pintype "passive"))
    )
    (net (code "100") (name "unconnected-(PWR-IN-Pad5)") (class "Default")
      (node (ref "PWR-IN") (pin "5") (pinfunction "5_5") (pintype "passive"))
    )
    (net (code "101") (name "unconnected-(PWR-IN-Pad6)") (class "Default")
      (node (ref "PWR-IN") (pin "6") (pinfunction "6_6") (pintype "passive"))
    )
    (net (code "102") (name "unconnected-(X3-Pad4)") (class "Default")
      (node (ref "X3") (pin "4") (pinfunction "4_4") (pintype "passive"))
    )
  )
)
